# Hub75_LED_Matrix_Adapter_for_ESP32_DevKi.net
KiCad netlist of a schematic drawn in EasyEDA
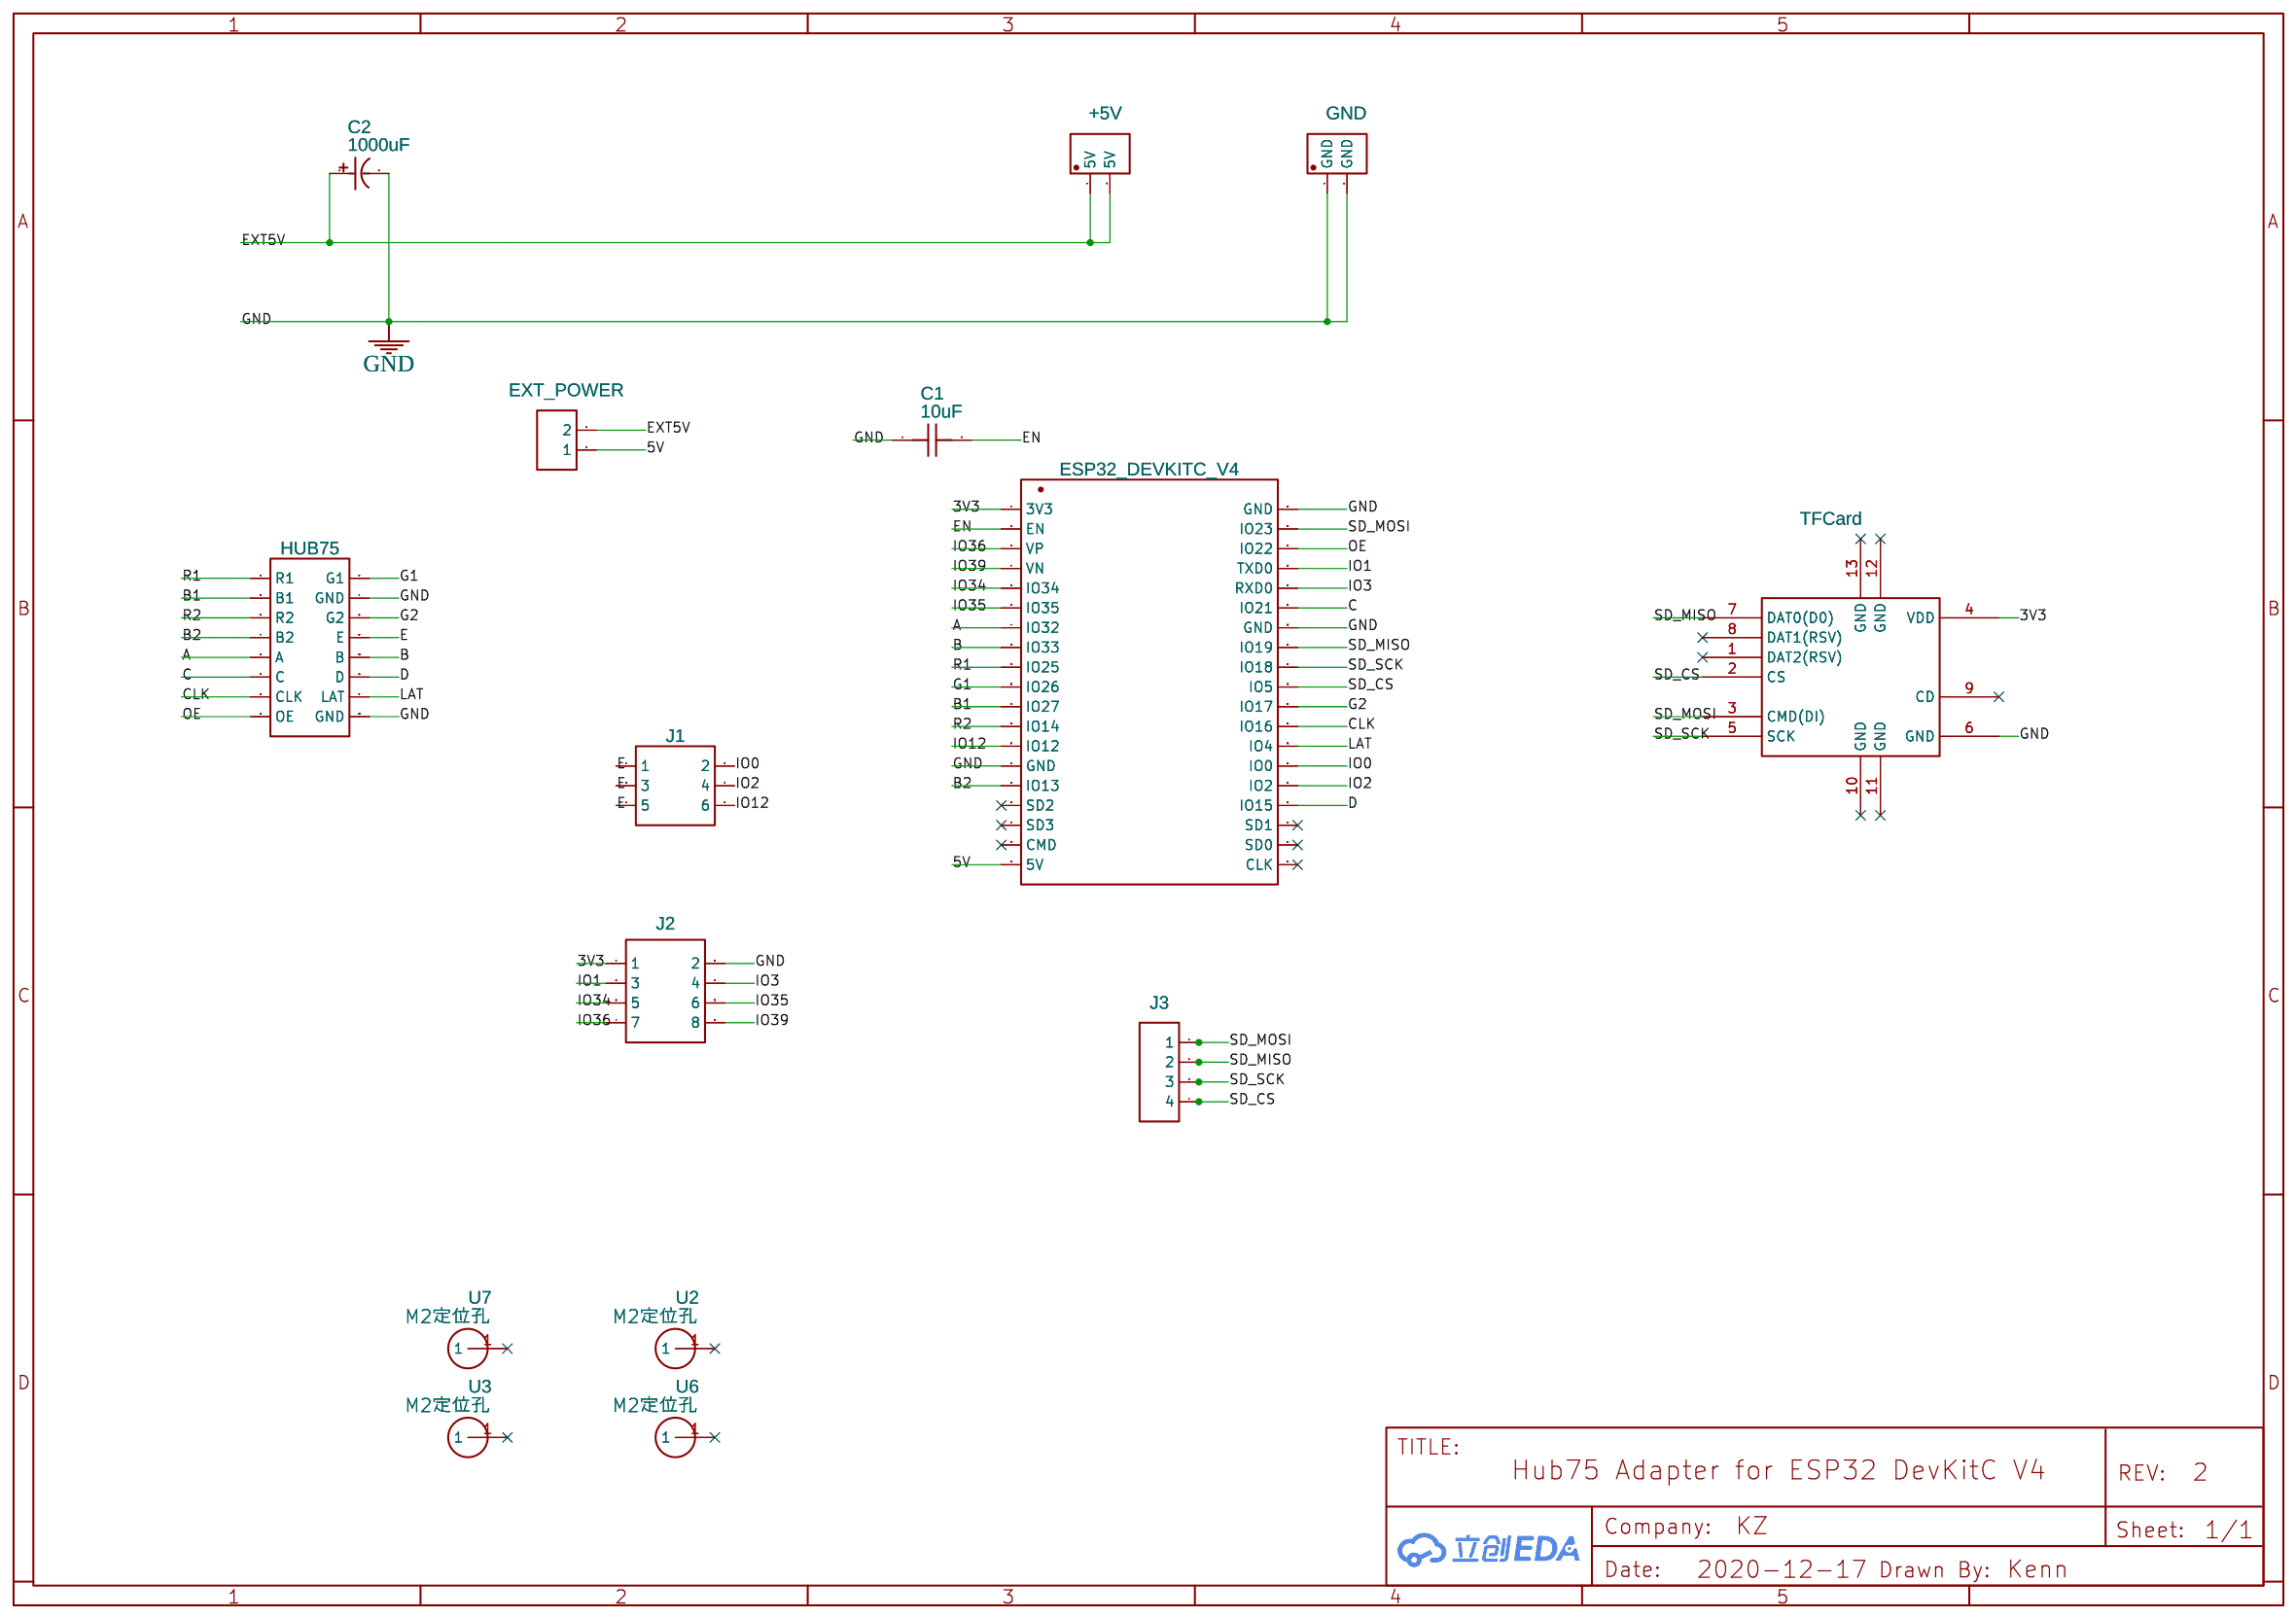
[diagram p0: schematic sheet]

(export (version "E")
  (design (tool "Eeschema 10.0.6"))
  (components
    (comp (ref "+5V")
      (value "WJ2EDGVC-5.08-2P")
      (fields (field (name "BOM_Supplier Part") "C8445"))
      (libsource (lib "") (part "Unknown_550_-730"))
    )
    (comp (ref "C1")
      (value "10uF")
      (fields
        (field (name "BOM_Manufacturer Part") "CGA5L3X5R1V106KT0Y0N")
        (field (name "BOM_Supplier Part") "C445690")
      )
      (libsource (lib "") (part "CGA5L3X5R1V106KT0Y0N"))
    )
    (comp (ref "C2")
      (value "1000uF")
      (fields (field (name "BOM_Manufacturer Part") "1000uF 16V") (field (name "BOM_Supplier Part") "C43909"))
      (libsource (lib "") (part "1000uF 16V"))
    )
    (comp (ref "CARD1")
      (value "TFCard")
      (fields (field (name "BOM_Manufacturer Part") "TF-015") (field (name "BOM_Supplier Part") "C113206"))
      (libsource (lib "") (part "TF-015"))
    )
    (comp (ref "ESP32_DEVKITC_V4")
      (value "ESP32-DevKitC V4 开发板")
      (fields
        (field (name "BOM_Manufacturer Part") "ESP32-DevKitC V4")
        (field (name "BOM_Supplier Part") "C571180")
      )
      (libsource (lib "") (part "ESP32-DevKitC V4 开发板"))
    )
    (comp (ref "EXT_POWER")
      (value "HDR-F-2.54_1x2")
      (fields (field (name "BOM_Supplier Part") "C49661"))
      (libsource (lib "") (part "HDR-F-2.54_1x2"))
    )
    (comp (ref "GND")
      (value "WJ2EDGVC-5.08-2P")
      (fields (field (name "BOM_Supplier Part") "C8445"))
      (libsource (lib "") (part "Unknown_670_-730"))
    )
    (comp (ref "HUB75")
      (value "HUB75-IDC-2.54-2X8P")
      (fields
        (field (name "BOM_Manufacturer Part") "IDC Box 2.54mm 16P　Straight")
        (field (name "BOM_Supplier Part") "C3406")
      )
      (libsource (lib "") (part "Unknown_150_-485"))
    )
    (comp (ref "J1")
      (value "HDR-M-2.54_2x3")
      (fields (field (name "BOM_Supplier Part") "C65114"))
      (libsource (lib "") (part "HDR-M-2.54_2x3"))
    )
    (comp (ref "J2")
      (value "HDR-M-2.54_2x4")
      (fields (field (name "BOM_Supplier Part") "C58363"))
      (libsource (lib "") (part "HDR-M-2.54_2x4"))
    )
    (comp (ref "J3")
      (value "HDR-M-2.54_1x4")
      (fields (field (name "BOM_Supplier Part") "C124378"))
      (libsource (lib "") (part "HDR-M-2.54_1x4"))
    )
    (comp (ref "U2") (value "M2定位孔") (libsource (lib "") (part "M2定位孔")))
    (comp (ref "U3") (value "M2定位孔") (libsource (lib "") (part "M2定位孔")))
    (comp (ref "U6") (value "M2定位孔") (libsource (lib "") (part "M2定位孔")))
    (comp (ref "U7") (value "M2定位孔") (libsource (lib "") (part "M2定位孔")))
  )
  (nets
    (net (code "1") (name "/3V3") (class "Default")
      (node (ref "CARD1") (pin "4") (pinfunction "VDD_4") (pintype "passive"))
      (node (ref "ESP32_DEVKITC_V4") (pin "1") (pinfunction "3V3_1") (pintype "passive"))
      (node (ref "J2") (pin "1") (pinfunction "1_1") (pintype "unspecified"))
    )
    (net (code "2") (name "/5V") (class "Default")
      (node (ref "ESP32_DEVKITC_V4") (pin "19") (pinfunction "5V_19") (pintype "passive"))
      (node (ref "EXT_POWER") (pin "1") (pinfunction "1_1") (pintype "input"))
    )
    (net (code "3") (name "/A") (class "Default")
      (node (ref "ESP32_DEVKITC_V4") (pin "7") (pinfunction "IO32_7") (pintype "unspecified"))
      (node (ref "HUB75") (pin "9") (pinfunction "A_9") (pintype "unspecified"))
    )
    (net (code "4") (name "/B") (class "Default")
      (node (ref "ESP32_DEVKITC_V4") (pin "8") (pinfunction "IO33_8") (pintype "unspecified"))
      (node (ref "HUB75") (pin "10") (pinfunction "B_10") (pintype "unspecified"))
    )
    (net (code "5") (name "/B1") (class "Default")
      (node (ref "ESP32_DEVKITC_V4") (pin "11") (pinfunction "IO27_11") (pintype "unspecified"))
      (node (ref "HUB75") (pin "3") (pinfunction "B1_3") (pintype "unspecified"))
    )
    (net (code "6") (name "/B2") (class "Default")
      (node (ref "ESP32_DEVKITC_V4") (pin "15") (pinfunction "IO13_15") (pintype "unspecified"))
      (node (ref "HUB75") (pin "7") (pinfunction "B2_7") (pintype "unspecified"))
    )
    (net (code "7") (name "/C") (class "Default")
      (node (ref "ESP32_DEVKITC_V4") (pin "33") (pinfunction "IO21_33") (pintype "unspecified"))
      (node (ref "HUB75") (pin "11") (pinfunction "C_11") (pintype "unspecified"))
    )
    (net (code "8") (name "/CLK") (class "Default")
      (node (ref "ESP32_DEVKITC_V4") (pin "27") (pinfunction "IO16_27") (pintype "unspecified"))
      (node (ref "HUB75") (pin "13") (pinfunction "CLK_13") (pintype "unspecified"))
    )
    (net (code "9") (name "/D") (class "Default")
      (node (ref "ESP32_DEVKITC_V4") (pin "23") (pinfunction "IO15_23") (pintype "unspecified"))
      (node (ref "HUB75") (pin "12") (pinfunction "D_12") (pintype "unspecified"))
    )
    (net (code "10") (name "/E") (class "Default")
      (node (ref "HUB75") (pin "8") (pinfunction "E_8") (pintype "unspecified"))
      (node (ref "J1") (pin "1") (pinfunction "1_1") (pintype "input"))
      (node (ref "J1") (pin "3") (pinfunction "3_3") (pintype "input"))
      (node (ref "J1") (pin "5") (pinfunction "5_5") (pintype "input"))
    )
    (net (code "11") (name "/EN") (class "Default")
      (node (ref "C1") (pin "2") (pinfunction "2_2") (pintype "unspecified"))
      (node (ref "ESP32_DEVKITC_V4") (pin "2") (pinfunction "EN_2") (pintype "unspecified"))
    )
    (net (code "12") (name "/EXT5V") (class "Default")
      (node (ref "+5V") (pin "1") (pinfunction "5V_1") (pintype "unspecified"))
      (node (ref "+5V") (pin "2") (pinfunction "5V_2") (pintype "unspecified"))
      (node (ref "C2") (pin "1") (pinfunction "1_1") (pintype "input"))
      (node (ref "EXT_POWER") (pin "2") (pinfunction "2_2") (pintype "input"))
    )
    (net (code "13") (name "/G1") (class "Default")
      (node (ref "ESP32_DEVKITC_V4") (pin "10") (pinfunction "IO26_10") (pintype "unspecified"))
      (node (ref "HUB75") (pin "2") (pinfunction "G1_2") (pintype "unspecified"))
    )
    (net (code "14") (name "/G2") (class "Default")
      (node (ref "ESP32_DEVKITC_V4") (pin "28") (pinfunction "IO17_28") (pintype "unspecified"))
      (node (ref "HUB75") (pin "6") (pinfunction "G2_6") (pintype "unspecified"))
    )
    (net (code "15") (name "/IO0") (class "Default")
      (node (ref "ESP32_DEVKITC_V4") (pin "25") (pinfunction "IO0_25") (pintype "unspecified"))
      (node (ref "J1") (pin "2") (pinfunction "2_2") (pintype "input"))
    )
    (net (code "16") (name "/IO1") (class "Default")
      (node (ref "ESP32_DEVKITC_V4") (pin "35") (pinfunction "TXD0_35") (pintype "unspecified"))
      (node (ref "J2") (pin "3") (pinfunction "3_3") (pintype "unspecified"))
    )
    (net (code "17") (name "/IO2") (class "Default")
      (node (ref "ESP32_DEVKITC_V4") (pin "24") (pinfunction "IO2_24") (pintype "unspecified"))
      (node (ref "J1") (pin "4") (pinfunction "4_4") (pintype "input"))
    )
    (net (code "18") (name "/IO3") (class "Default")
      (node (ref "ESP32_DEVKITC_V4") (pin "34") (pinfunction "RXD0_34") (pintype "unspecified"))
      (node (ref "J2") (pin "4") (pinfunction "4_4") (pintype "unspecified"))
    )
    (net (code "19") (name "/IO12") (class "Default")
      (node (ref "ESP32_DEVKITC_V4") (pin "13") (pinfunction "IO12_13") (pintype "unspecified"))
      (node (ref "J1") (pin "6") (pinfunction "6_6") (pintype "input"))
    )
    (net (code "20") (name "/IO34") (class "Default")
      (node (ref "ESP32_DEVKITC_V4") (pin "5") (pinfunction "IO34_5") (pintype "unspecified"))
      (node (ref "J2") (pin "5") (pinfunction "5_5") (pintype "unspecified"))
    )
    (net (code "21") (name "/IO35") (class "Default")
      (node (ref "ESP32_DEVKITC_V4") (pin "6") (pinfunction "IO35_6") (pintype "unspecified"))
      (node (ref "J2") (pin "6") (pinfunction "6_6") (pintype "unspecified"))
    )
    (net (code "22") (name "/IO36") (class "Default")
      (node (ref "ESP32_DEVKITC_V4") (pin "3") (pinfunction "VP_3") (pintype "unspecified"))
      (node (ref "J2") (pin "7") (pinfunction "7_7") (pintype "unspecified"))
    )
    (net (code "23") (name "/IO39") (class "Default")
      (node (ref "ESP32_DEVKITC_V4") (pin "4") (pinfunction "VN_4") (pintype "unspecified"))
      (node (ref "J2") (pin "8") (pinfunction "8_8") (pintype "unspecified"))
    )
    (net (code "24") (name "/LAT") (class "Default")
      (node (ref "ESP32_DEVKITC_V4") (pin "26") (pinfunction "IO4_26") (pintype "unspecified"))
      (node (ref "HUB75") (pin "14") (pinfunction "LAT_14") (pintype "unspecified"))
    )
    (net (code "25") (name "/OE") (class "Default")
      (node (ref "ESP32_DEVKITC_V4") (pin "36") (pinfunction "IO22_36") (pintype "unspecified"))
      (node (ref "HUB75") (pin "15") (pinfunction "OE_15") (pintype "unspecified"))
    )
    (net (code "26") (name "/R1") (class "Default")
      (node (ref "ESP32_DEVKITC_V4") (pin "9") (pinfunction "IO25_9") (pintype "unspecified"))
      (node (ref "HUB75") (pin "1") (pinfunction "R1_1") (pintype "unspecified"))
    )
    (net (code "27") (name "/R2") (class "Default")
      (node (ref "ESP32_DEVKITC_V4") (pin "12") (pinfunction "IO14_12") (pintype "unspecified"))
      (node (ref "HUB75") (pin "5") (pinfunction "R2_5") (pintype "unspecified"))
    )
    (net (code "28") (name "/SD_CS") (class "Default")
      (node (ref "CARD1") (pin "2") (pinfunction "CS_2") (pintype "bidirectional"))
      (node (ref "ESP32_DEVKITC_V4") (pin "29") (pinfunction "IO5_29") (pintype "unspecified"))
      (node (ref "J3") (pin "4") (pinfunction "4_4") (pintype "unspecified"))
    )
    (net (code "29") (name "/SD_MISO") (class "Default")
      (node (ref "CARD1") (pin "7") (pinfunction "DAT0(D0)_7") (pintype "bidirectional"))
      (node (ref "ESP32_DEVKITC_V4") (pin "31") (pinfunction "IO19_31") (pintype "unspecified"))
      (node (ref "J3") (pin "2") (pinfunction "2_2") (pintype "unspecified"))
    )
    (net (code "30") (name "/SD_MOSI") (class "Default")
      (node (ref "CARD1") (pin "3") (pinfunction "CMD(DI)_3") (pintype "input"))
      (node (ref "ESP32_DEVKITC_V4") (pin "37") (pinfunction "IO23_37") (pintype "unspecified"))
      (node (ref "J3") (pin "1") (pinfunction "1_1") (pintype "unspecified"))
    )
    (net (code "31") (name "/SD_SCK") (class "Default")
      (node (ref "CARD1") (pin "5") (pinfunction "SCK_5") (pintype "input"))
      (node (ref "ESP32_DEVKITC_V4") (pin "30") (pinfunction "IO18_30") (pintype "unspecified"))
      (node (ref "J3") (pin "3") (pinfunction "3_3") (pintype "unspecified"))
    )
    (net (code "32") (name "GND") (class "Default")
      (node (ref "C1") (pin "1") (pinfunction "1_1") (pintype "unspecified"))
      (node (ref "C2") (pin "2") (pinfunction "2_2") (pintype "input"))
      (node (ref "CARD1") (pin "6") (pinfunction "GND_6") (pintype "passive"))
      (node (ref "ESP32_DEVKITC_V4") (pin "14") (pinfunction "GND_14") (pintype "unspecified"))
      (node (ref "ESP32_DEVKITC_V4") (pin "32") (pinfunction "GND_32") (pintype "unspecified"))
      (node (ref "ESP32_DEVKITC_V4") (pin "38") (pinfunction "GND_38") (pintype "unspecified"))
      (node (ref "GND") (pin "1") (pinfunction "GND_1") (pintype "unspecified"))
      (node (ref "GND") (pin "2") (pinfunction "GND_2") (pintype "unspecified"))
      (node (ref "HUB75") (pin "16") (pinfunction "GND_16") (pintype "unspecified"))
      (node (ref "HUB75") (pin "4") (pinfunction "GND_4") (pintype "unspecified"))
      (node (ref "J2") (pin "2") (pinfunction "2_2") (pintype "unspecified"))
    )
    (net (code "33") (name "unconnected-(CARD1-CD-Pad9)") (class "Default")
      (node (ref "CARD1") (pin "9") (pinfunction "CD_9") (pintype "input+no_connect"))
    )
    (net (code "34") (name "unconnected-(CARD1-DAT1(RSV)-Pad8)") (class "Default")
      (node (ref "CARD1") (pin "8") (pinfunction "DAT1(RSV)_8") (pintype "bidirectional+no_connect"))
    )
    (net (code "35") (name "unconnected-(CARD1-DAT2(RSV)-Pad1)") (class "Default")
      (node (ref "CARD1") (pin "1") (pinfunction "DAT2(RSV)_1") (pintype "unspecified+no_connect"))
    )
    (net (code "36") (name "unconnected-(CARD1-GND-Pad10)") (class "Default")
      (node (ref "CARD1") (pin "10") (pinfunction "GND_10") (pintype "input+no_connect"))
    )
    (net (code "37") (name "unconnected-(CARD1-GND-Pad11)") (class "Default")
      (node (ref "CARD1") (pin "11") (pinfunction "GND_11") (pintype "input+no_connect"))
    )
    (net (code "38") (name "unconnected-(CARD1-GND-Pad12)") (class "Default")
      (node (ref "CARD1") (pin "12") (pinfunction "GND_12") (pintype "input+no_connect"))
    )
    (net (code "39") (name "unconnected-(CARD1-GND-Pad13)") (class "Default")
      (node (ref "CARD1") (pin "13") (pinfunction "GND_13") (pintype "input+no_connect"))
    )
    (net (code "40") (name "unconnected-(ESP32_DEVKITC_V4-CLK-Pad20)") (class "Default")
      (node (ref "ESP32_DEVKITC_V4") (pin "20") (pinfunction "CLK_20") (pintype "unspecified+no_connect"))
    )
    (net (code "41") (name "unconnected-(ESP32_DEVKITC_V4-CMD-Pad18)") (class "Default")
      (node (ref "ESP32_DEVKITC_V4") (pin "18") (pinfunction "CMD_18") (pintype "unspecified+no_connect"))
    )
    (net (code "42") (name "unconnected-(ESP32_DEVKITC_V4-SD0-Pad21)") (class "Default")
      (node (ref "ESP32_DEVKITC_V4") (pin "21") (pinfunction "SD0_21") (pintype "unspecified+no_connect"))
    )
    (net (code "43") (name "unconnected-(ESP32_DEVKITC_V4-SD1-Pad22)") (class "Default")
      (node (ref "ESP32_DEVKITC_V4") (pin "22") (pinfunction "SD1_22") (pintype "unspecified+no_connect"))
    )
    (net (code "44") (name "unconnected-(ESP32_DEVKITC_V4-SD2-Pad16)") (class "Default")
      (node (ref "ESP32_DEVKITC_V4") (pin "16") (pinfunction "SD2_16") (pintype "unspecified+no_connect"))
    )
    (net (code "45") (name "unconnected-(ESP32_DEVKITC_V4-SD3-Pad17)") (class "Default")
      (node (ref "ESP32_DEVKITC_V4") (pin "17") (pinfunction "SD3_17") (pintype "unspecified+no_connect"))
    )
    (net (code "46") (name "unconnected-(U2-Pad1)") (class "Default")
      (node (ref "U2") (pin "1") (pinfunction "1_1") (pintype "unspecified+no_connect"))
    )
    (net (code "47") (name "unconnected-(U3-Pad1)") (class "Default")
      (node (ref "U3") (pin "1") (pinfunction "1_1") (pintype "unspecified+no_connect"))
    )
    (net (code "48") (name "unconnected-(U6-Pad1)") (class "Default")
      (node (ref "U6") (pin "1") (pinfunction "1_1") (pintype "unspecified+no_connect"))
    )
    (net (code "49") (name "unconnected-(U7-Pad1)") (class "Default")
      (node (ref "U7") (pin "1") (pinfunction "1_1") (pintype "unspecified+no_connect"))
    )
  )
)
